# power_dist.net
KiCad netlist of a schematic drawn in EAGLE
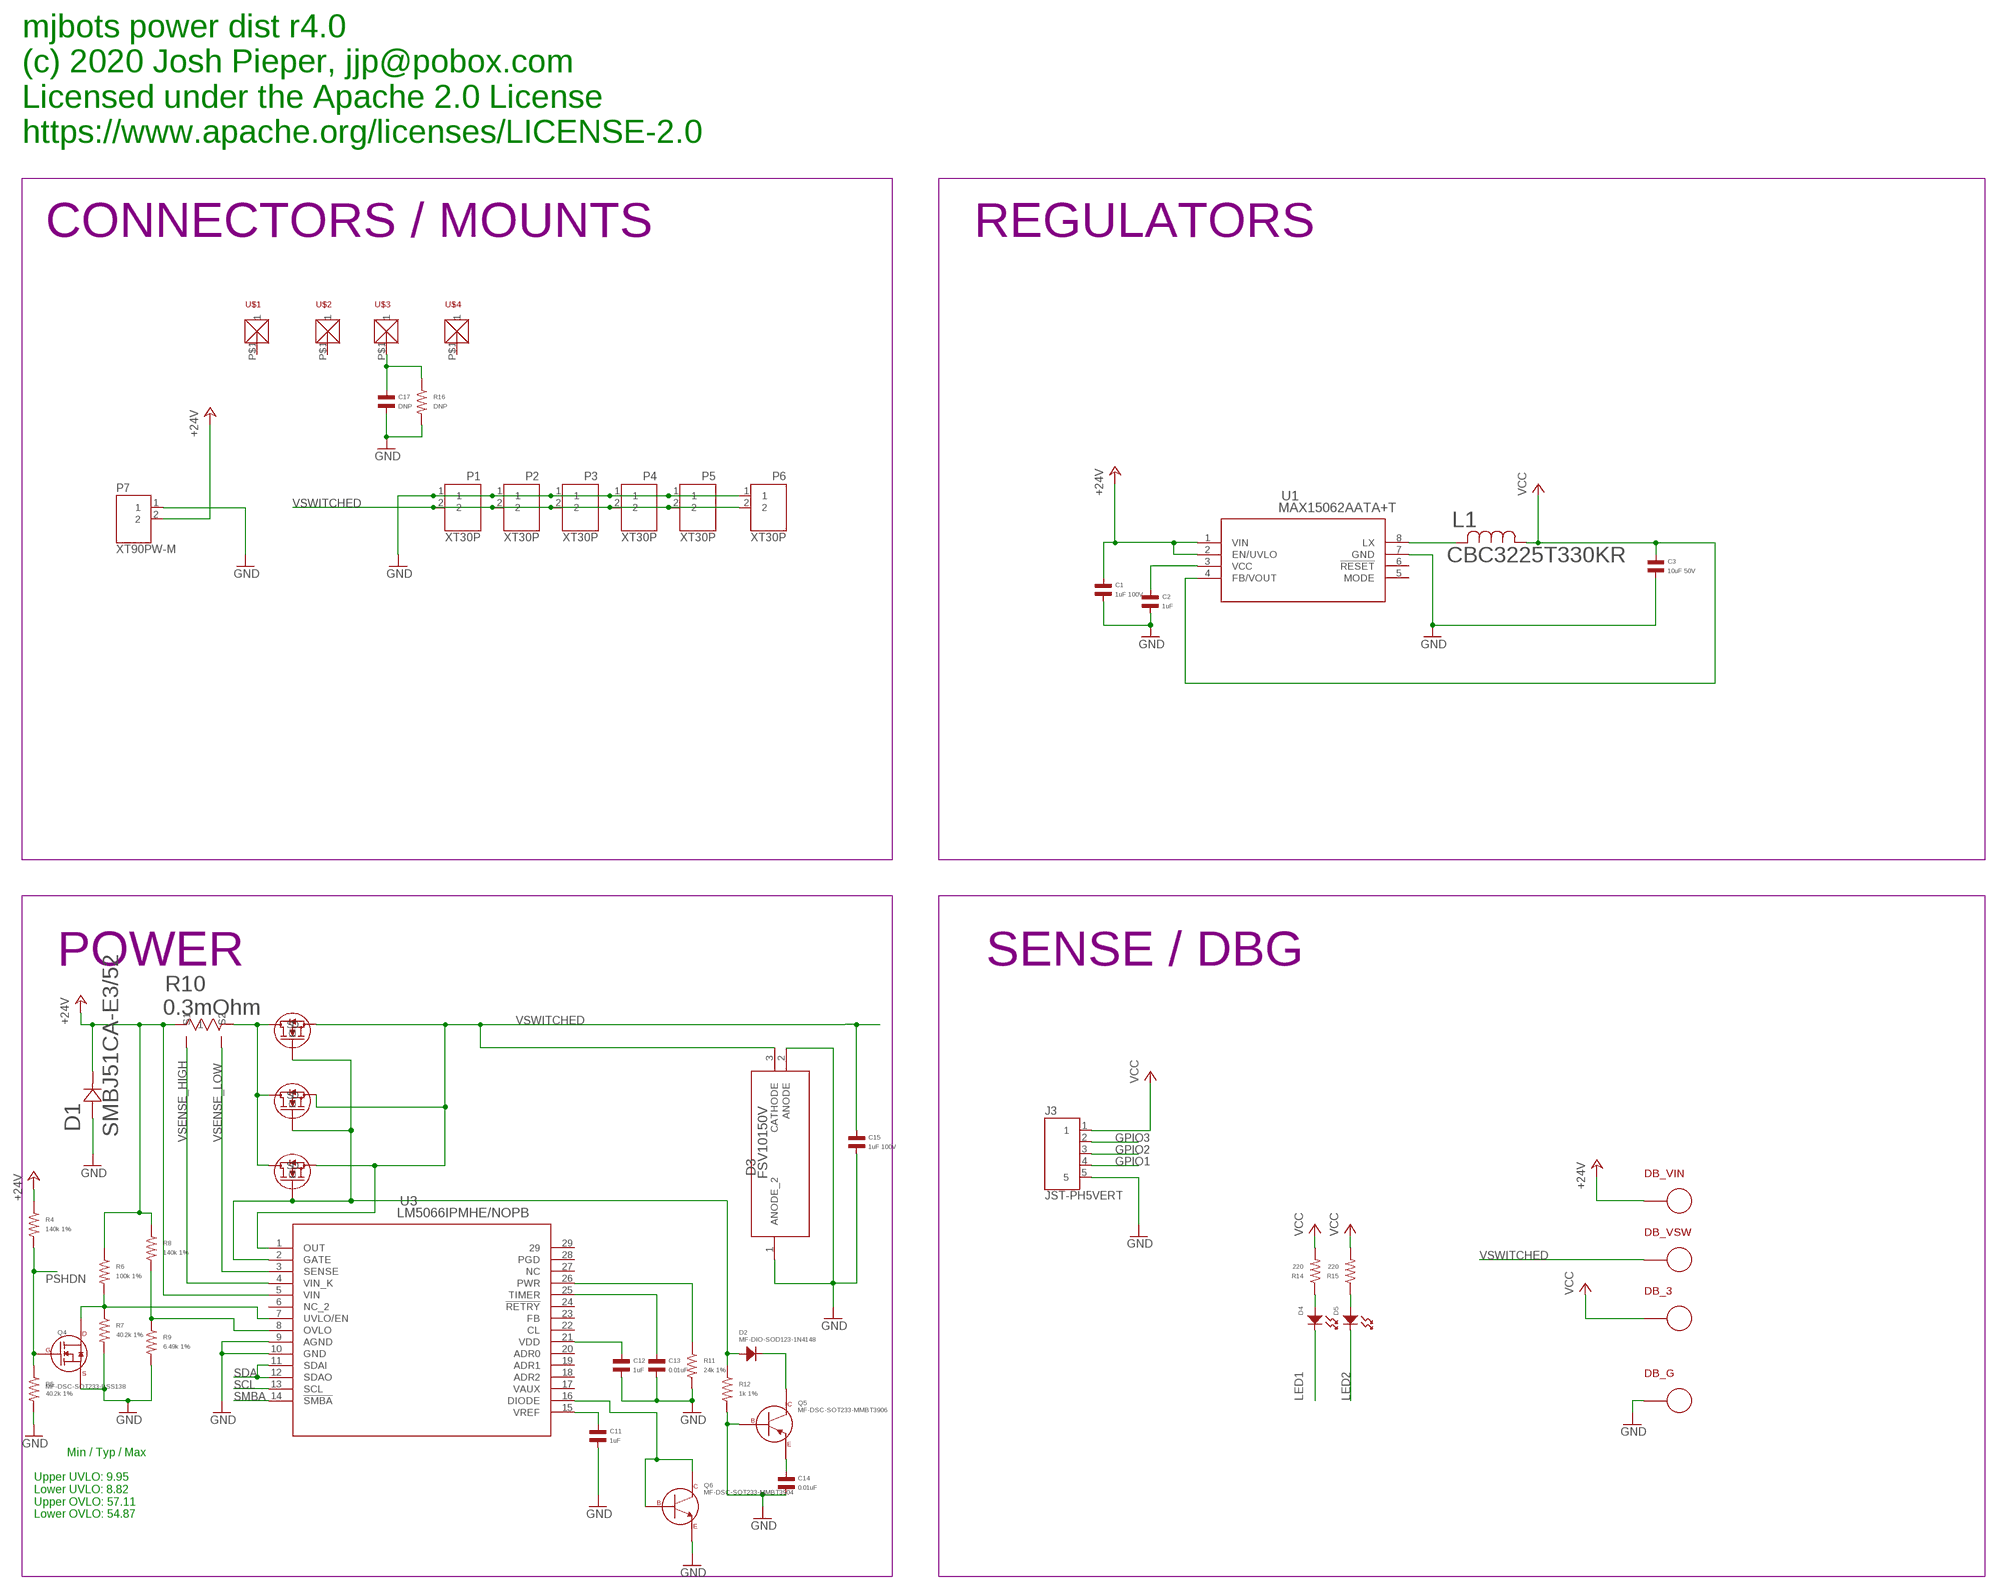
[diagram p0: schematic, sheet 1, part 1 of 2]
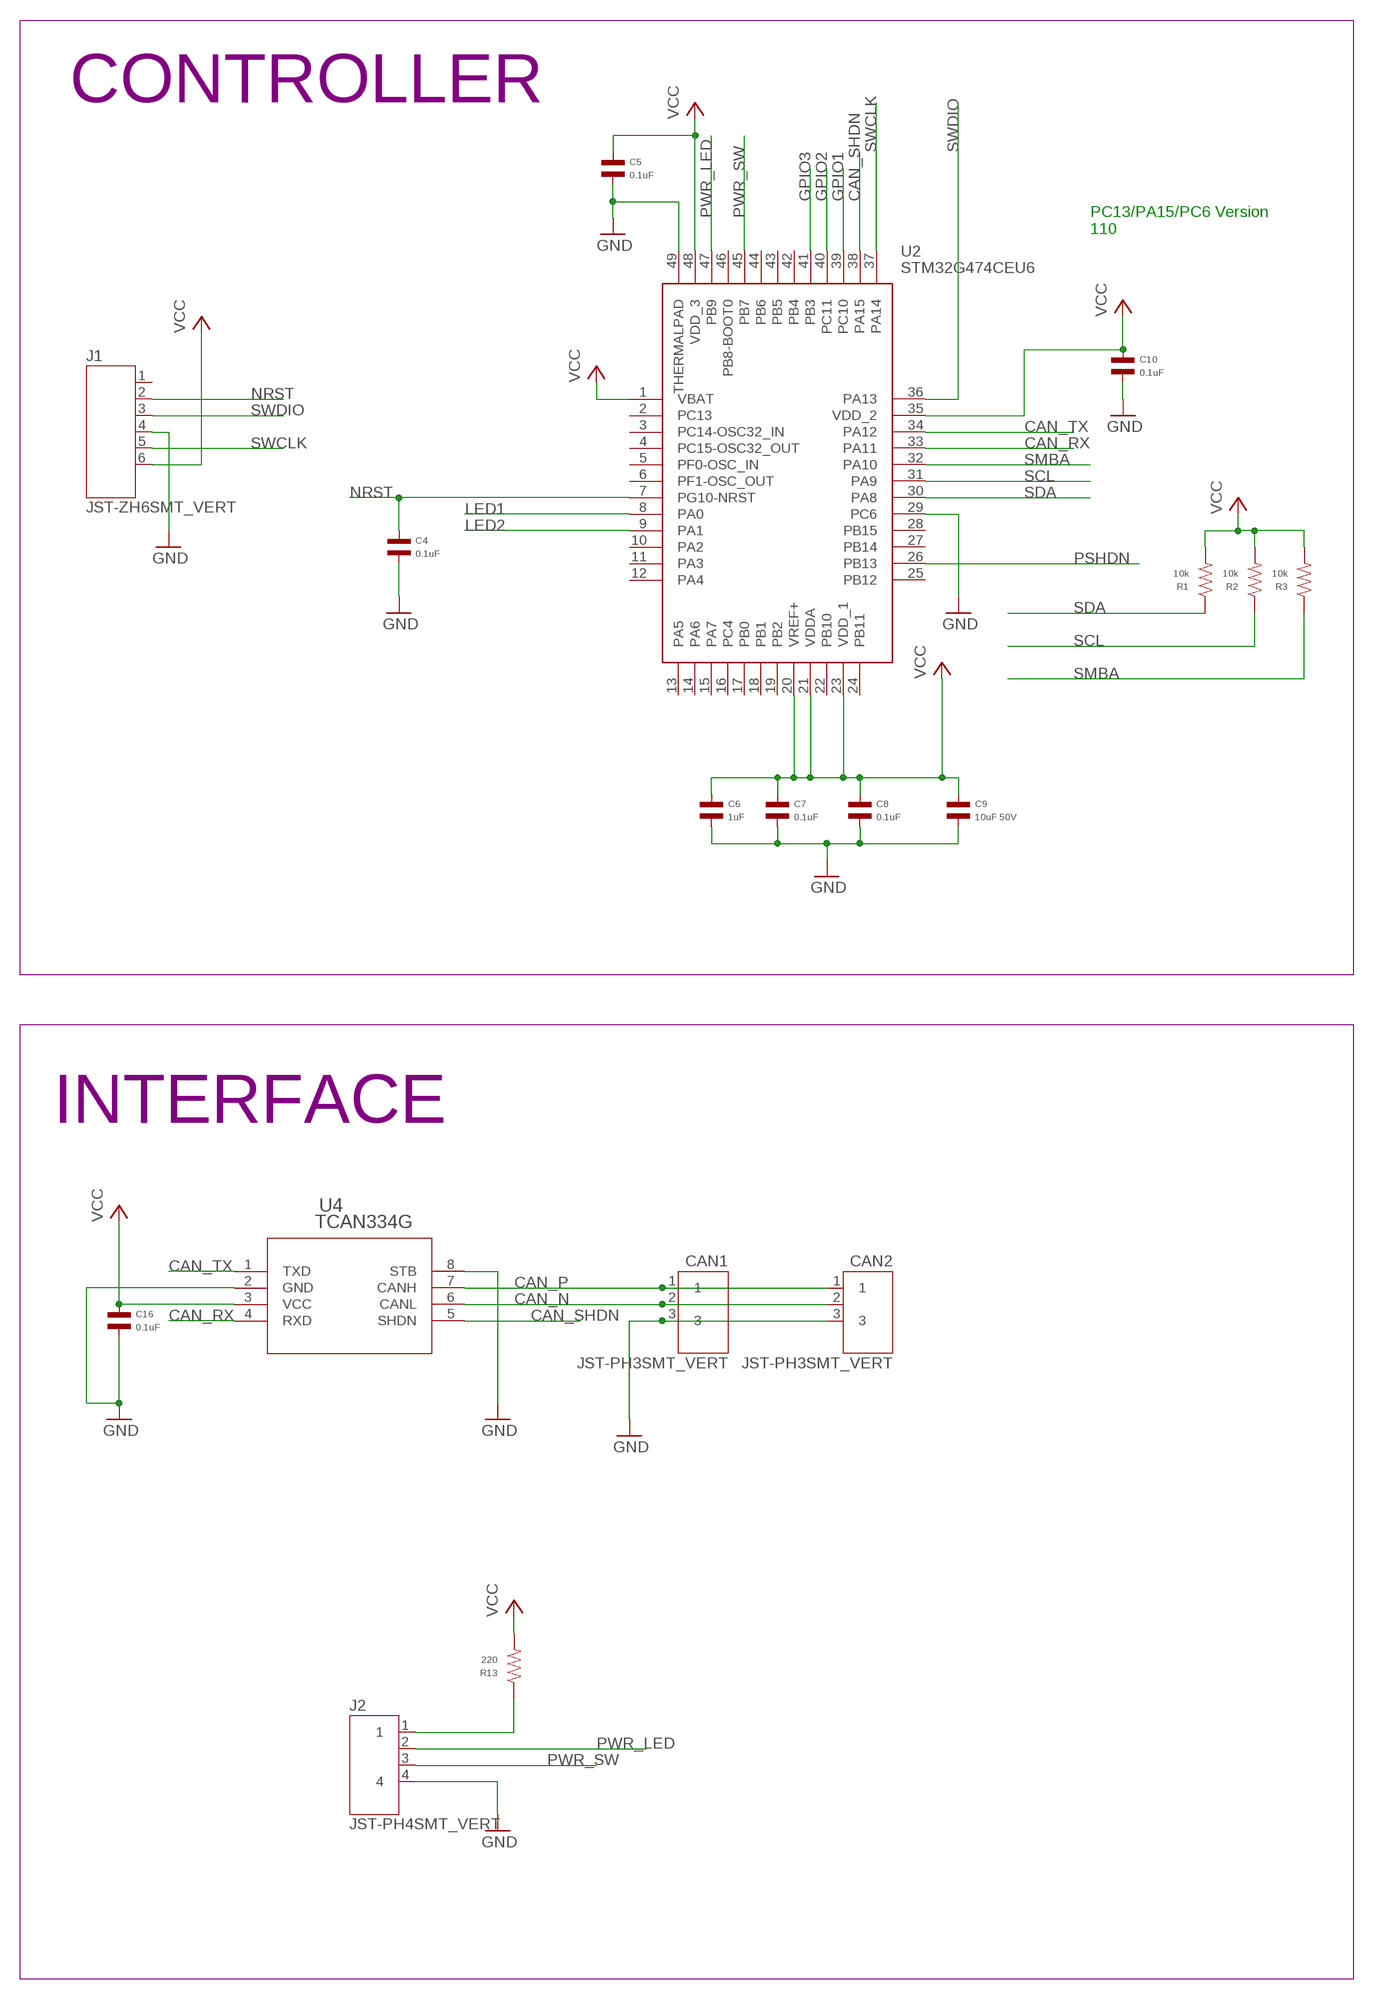
[diagram p1: schematic, sheet 1, part 2 of 2]

(export (version "E")
  (design (tool "Eeschema 10.0.6"))
  (components
    (comp (ref "C1")
      (value "1uF 100V")
      (footprint "eagle-import:C0805")
      (fields (field (name "MF") "MURATA") (field (name "MPN") "GCM21BC72A105KE36L"))
      (libsource (lib "eagle-import") (part "CAPACITOR_NP_0805"))
    )
    (comp (ref "C2")
      (value "1uF")
      (footprint "eagle-import:C0603")
      (fields (field (name "HOUSEPART") "1") (field (name "MPN") "MF-CAP-0603-1uF"))
      (libsource (lib "eagle-import") (part "CAPACITOR_NP_0603"))
    )
    (comp (ref "C3")
      (value "10uF 50V")
      (footprint "eagle-import:C1206")
      (fields (field (name "MF") "TDK") (field (name "MPN") "C3216X7R1H106K160AE"))
      (libsource (lib "eagle-import") (part "CAPACITOR_NP_1206"))
    )
    (comp (ref "C4")
      (value "0.1uF")
      (footprint "eagle-import:C0603")
      (fields (field (name "HOUSEPART") "1") (field (name "MPN") "MF-CAP-0603-0.1uF"))
      (libsource (lib "eagle-import") (part "CAPACITOR_NP_0603"))
    )
    (comp (ref "C5")
      (value "0.1uF")
      (footprint "eagle-import:C0603")
      (fields (field (name "HOUSEPART") "1") (field (name "MPN") "MF-CAP-0603-0.1uF"))
      (libsource (lib "eagle-import") (part "CAPACITOR_NP_0603"))
    )
    (comp (ref "C6")
      (value "1uF")
      (footprint "eagle-import:C0603")
      (fields (field (name "HOUSEPART") "1") (field (name "MPN") "MF-CAP-0603-1uF"))
      (libsource (lib "eagle-import") (part "CAPACITOR_NP_0603"))
    )
    (comp (ref "C7")
      (value "0.1uF")
      (footprint "eagle-import:C0603")
      (fields (field (name "HOUSEPART") "1") (field (name "MPN") "MF-CAP-0603-0.1uF"))
      (libsource (lib "eagle-import") (part "CAPACITOR_NP_0603"))
    )
    (comp (ref "C8")
      (value "0.1uF")
      (footprint "eagle-import:C0603")
      (fields (field (name "HOUSEPART") "1") (field (name "MPN") "MF-CAP-0603-0.1uF"))
      (libsource (lib "eagle-import") (part "CAPACITOR_NP_0603"))
    )
    (comp (ref "C9")
      (value "10uF 50V")
      (footprint "eagle-import:C1206")
      (fields (field (name "MF") "TDK") (field (name "MPN") "C3216X7R1H106K160AE"))
      (libsource (lib "eagle-import") (part "CAPACITOR_NP_1206"))
    )
    (comp (ref "C10")
      (value "0.1uF")
      (footprint "eagle-import:C0603")
      (fields (field (name "HOUSEPART") "1") (field (name "MPN") "MF-CAP-0603-0.1uF"))
      (libsource (lib "eagle-import") (part "CAPACITOR_NP_0603"))
    )
    (comp (ref "C11")
      (value "1uF")
      (footprint "eagle-import:C0603")
      (fields (field (name "HOUSEPART") "1") (field (name "MPN") "MF-CAP-0603-1uF"))
      (libsource (lib "eagle-import") (part "CAPACITOR_NP_0603"))
    )
    (comp (ref "C12")
      (value "1uF")
      (footprint "eagle-import:C0603")
      (fields (field (name "HOUSEPART") "1") (field (name "MPN") "MF-CAP-0603-1uF"))
      (libsource (lib "eagle-import") (part "CAPACITOR_NP_0603"))
    )
    (comp (ref "C13")
      (value "0.01uF")
      (footprint "eagle-import:C0603")
      (fields (field (name "HOUSEPART") "1") (field (name "MPN") "MF-CAP-0603-0.01uF"))
      (libsource (lib "eagle-import") (part "CAPACITOR_NP_0603"))
    )
    (comp (ref "C14")
      (value "0.01uF")
      (footprint "eagle-import:C0603")
      (fields (field (name "HOUSEPART") "1") (field (name "MPN") "MF-CAP-0603-0.01uF"))
      (libsource (lib "eagle-import") (part "CAPACITOR_NP_0603"))
    )
    (comp (ref "C15")
      (value "1uF 100V")
      (footprint "eagle-import:C0805")
      (fields (field (name "MF") "MURATA") (field (name "MPN") "GCM21BC72A105KE36L"))
      (libsource (lib "eagle-import") (part "CAPACITOR_NP_0805"))
    )
    (comp (ref "C16")
      (value "0.1uF")
      (footprint "eagle-import:C0603")
      (fields (field (name "HOUSEPART") "1") (field (name "MPN") "MF-CAP-0603-0.1uF"))
      (libsource (lib "eagle-import") (part "CAPACITOR_NP_0603"))
    )
    (comp (ref "C17")
      (value "DNP")
      (footprint "eagle-import:C0603")
      (fields (field (name "POPULATE") "0"))
      (libsource (lib "eagle-import") (part "CAPACITOR_NP_0603"))
    )
    (comp (ref "CAN1")
      (value "JST-PH3SMT_VERT")
      (footprint "eagle-import:JST_B3B_PH-SM4-TB(LF)(SN)")
      (fields (field (name "MF") "JST") (field (name "MPN") "B3B-PH-SM4-TB(LF)(SN)"))
      (libsource (lib "eagle-import") (part "JST-PH3SMT_VERT"))
    )
    (comp (ref "CAN2")
      (value "JST-PH3SMT_VERT")
      (footprint "eagle-import:JST_B3B_PH-SM4-TB(LF)(SN)")
      (fields (field (name "MF") "JST") (field (name "MPN") "B3B-PH-SM4-TB(LF)(SN)"))
      (libsource (lib "eagle-import") (part "JST-PH3SMT_VERT"))
    )
    (comp (ref "D1")
      (value "SMBJ51CA-E3/52")
      (footprint "eagle-import:DIODE_DO-214AC")
      (libsource (lib "eagle-import") (part "SMBJ51CA-E3/52"))
    )
    (comp (ref "D2")
      (value "MF-DIO-SOD123-1N4148")
      (footprint "eagle-import:SOD-123")
      (fields (field (name "HOUSEPART") "YES") (field (name "HOUSEPART_1") "1"))
      (libsource (lib "eagle-import") (part "DIODES_SOD-123_1N4148"))
    )
    (comp (ref "D3")
      (value "FSV10150V")
      (footprint "eagle-import:TO277-3L_ONS")
      (fields (field (name "COPYRIGHT") "Copyright (C) 2018 Accelerated Designs. All rights reserved"))
      (libsource (lib "eagle-import") (part "FSV10150V"))
    )
    (comp (ref "D4")
      (value "LED_SINGLE-0603")
      (footprint "eagle-import:LED0603")
      (fields
        (field (name "HOUSEPART") "NO")
        (field (name "HOUSEPART_1") "1")
        (field (name "MPN") "MF-LED-0603-RED")
      )
      (libsource (lib "eagle-import") (part "LED_SINGLE-0603"))
    )
    (comp (ref "D5")
      (value "LED_SINGLE-0603")
      (footprint "eagle-import:LED0603")
      (fields
        (field (name "HOUSEPART") "NO")
        (field (name "HOUSEPART_1") "1")
        (field (name "MPN") "MF-LED-0603-RED")
      )
      (libsource (lib "eagle-import") (part "LED_SINGLE-0603"))
    )
    (comp (ref "DB_3")
      (value "PAD24AWG_PAD")
      (footprint "eagle-import:24AWG_PAD")
      (libsource (lib "eagle-import") (part "PAD24AWG_PAD"))
    )
    (comp (ref "DB_G")
      (value "PAD24AWG_PAD")
      (footprint "eagle-import:24AWG_PAD")
      (libsource (lib "eagle-import") (part "PAD24AWG_PAD"))
    )
    (comp (ref "DB_VIN")
      (value "PAD24AWG_PAD")
      (footprint "eagle-import:24AWG_PAD")
      (libsource (lib "eagle-import") (part "PAD24AWG_PAD"))
    )
    (comp (ref "DB_VSW")
      (value "PAD24AWG_PAD")
      (footprint "eagle-import:24AWG_PAD")
      (libsource (lib "eagle-import") (part "PAD24AWG_PAD"))
    )
    (comp (ref "J1")
      (value "JST-ZH6SMT_VERT")
      (footprint "eagle-import:JST_B6B-ZR-SM4-TF(LF)(SN)")
      (fields (field (name "MF") "JST") (field (name "MPN") "B6B-ZR-SM4-TF(LF)(SN)"))
      (libsource (lib "eagle-import") (part "JST-ZH6SMT_VERT"))
    )
    (comp (ref "J2")
      (value "JST-PH4SMT_VERT")
      (footprint "eagle-import:JST_B4B_PH-SM4-TB(LF)(SN)")
      (fields (field (name "MF") "JST") (field (name "MPN") "B4B-PH-SM4-TB(LF)(SN)"))
      (libsource (lib "eagle-import") (part "JST-PH4SMT_VERT"))
    )
    (comp (ref "J3")
      (value "JST-PH5VERT")
      (footprint "eagle-import:JST_B5B_PH-SM4-TB(LF)(SN)")
      (fields (field (name "MF") "JST") (field (name "MPN") "B5B-PH-SM4-TB(LF)(SN)"))
      (libsource (lib "eagle-import") (part "JST-PH5VERT"))
    )
    (comp (ref "L1")
      (value "CBC3225T330KR")
      (footprint "eagle-import:IND_TAIYO_CBC3225_TAY")
      (libsource (lib "eagle-import") (part "CBC3225T330KR"))
    )
    (comp (ref "P1")
      (value "XT30P")
      (footprint "eagle-import:XT30P")
      (fields (field (name "MF") "AMASS") (field (name "MPN") "XT30UPB-F"))
      (libsource (lib "eagle-import") (part "XT30P"))
    )
    (comp (ref "P2")
      (value "XT30P")
      (footprint "eagle-import:XT30P")
      (fields (field (name "MF") "AMASS") (field (name "MPN") "XT30UPB-F"))
      (libsource (lib "eagle-import") (part "XT30P"))
    )
    (comp (ref "P3")
      (value "XT30P")
      (footprint "eagle-import:XT30P")
      (fields (field (name "MF") "AMASS") (field (name "MPN") "XT30UPB-F"))
      (libsource (lib "eagle-import") (part "XT30P"))
    )
    (comp (ref "P4")
      (value "XT30P")
      (footprint "eagle-import:XT30P")
      (fields (field (name "MF") "AMASS") (field (name "MPN") "XT30UPB-F"))
      (libsource (lib "eagle-import") (part "XT30P"))
    )
    (comp (ref "P5")
      (value "XT30P")
      (footprint "eagle-import:XT30P")
      (fields (field (name "MF") "AMASS") (field (name "MPN") "XT30UPB-F"))
      (libsource (lib "eagle-import") (part "XT30P"))
    )
    (comp (ref "P6")
      (value "XT30P")
      (footprint "eagle-import:XT30P")
      (fields (field (name "MF") "AMASS") (field (name "MPN") "XT30UPB-F"))
      (libsource (lib "eagle-import") (part "XT30P"))
    )
    (comp (ref "P7")
      (value "XT90PW-M")
      (footprint "eagle-import:XT90PW-M")
      (libsource (lib "eagle-import") (part "XT90PW-M"))
    )
    (comp (ref "Q1")
      (value "PSMN4R8-100BSEJ")
      (footprint "eagle-import:D2PAK_SOT404_NEX")
      (fields (field (name "COPYRIGHT") "Copyright (C) 2018 Accelerated Designs. All rights reserved"))
      (libsource (lib "eagle-import") (part "PSMN4R8-100BSEJ"))
    )
    (comp (ref "Q2")
      (value "PSMN4R8-100BSEJ")
      (footprint "eagle-import:D2PAK_SOT404_NEX")
      (fields (field (name "COPYRIGHT") "Copyright (C) 2018 Accelerated Designs. All rights reserved"))
      (libsource (lib "eagle-import") (part "PSMN4R8-100BSEJ"))
    )
    (comp (ref "Q3")
      (value "PSMN4R8-100BSEJ")
      (footprint "eagle-import:D2PAK_SOT404_NEX")
      (fields (field (name "COPYRIGHT") "Copyright (C) 2018 Accelerated Designs. All rights reserved"))
      (libsource (lib "eagle-import") (part "PSMN4R8-100BSEJ"))
    )
    (comp (ref "Q4")
      (value "MF-DSC-SOT233-BSS138")
      (footprint "eagle-import:SOT-23-3")
      (fields (field (name "HOUSEPART") "YES") (field (name "HOUSEPART_1") "1"))
      (libsource (lib "eagle-import") (part "N-CHANNEL_FET_SOT-23-3_BSS138"))
    )
    (comp (ref "Q5")
      (value "MF-DSC-SOT233-MMBT3906")
      (footprint "eagle-import:SOT-23-3")
      (fields (field (name "HOUSEPART") "YES") (field (name "HOUSEPART_1") "1"))
      (libsource (lib "eagle-import") (part "PNP_BJT_SOT-23-3_MMBT3906"))
    )
    (comp (ref "Q6")
      (value "MF-DSC-SOT233-MMBT3904")
      (footprint "eagle-import:SOT-23-3")
      (fields (field (name "HOUSEPART") "YES") (field (name "HOUSEPART_1") "1"))
      (libsource (lib "eagle-import") (part "NPN_BJT_SOT-23-3MMBT3904"))
    )
    (comp (ref "R1")
      (value "10k")
      (footprint "eagle-import:R0603")
      (fields (field (name "HOUSEPART") "1") (field (name "MPN") "MF-RES-0603-10K"))
      (libsource (lib "eagle-import") (part "RESISTOR_0603"))
    )
    (comp (ref "R2")
      (value "10k")
      (footprint "eagle-import:R0603")
      (fields (field (name "HOUSEPART") "1") (field (name "MPN") "MF-RES-0603-10K"))
      (libsource (lib "eagle-import") (part "RESISTOR_0603"))
    )
    (comp (ref "R3")
      (value "10k")
      (footprint "eagle-import:R0603")
      (fields (field (name "HOUSEPART") "1") (field (name "MPN") "MF-RES-0603-10K"))
      (libsource (lib "eagle-import") (part "RESISTOR_0603"))
    )
    (comp (ref "R4")
      (value "140k 1%")
      (footprint "eagle-import:R0603")
      (fields (field (name "MF") "YAGEO") (field (name "MPN") "RC0603FR-07140KL"))
      (libsource (lib "eagle-import") (part "RESISTOR_0603"))
    )
    (comp (ref "R5")
      (value "40.2k 1%")
      (footprint "eagle-import:R0603")
      (fields (field (name "MF") "YAGEO") (field (name "MPN") "RC0603FR-0740K2L"))
      (libsource (lib "eagle-import") (part "RESISTOR_0603"))
    )
    (comp (ref "R6")
      (value "100k 1%")
      (footprint "eagle-import:R0603")
      (fields (field (name "MF") "YAGEO") (field (name "MPN") "RC0603FR-07100KL"))
      (libsource (lib "eagle-import") (part "RESISTOR_0603"))
    )
    (comp (ref "R7")
      (value "40.2k 1%")
      (footprint "eagle-import:R0603")
      (fields (field (name "MF") "YAGEO") (field (name "MPN") "RC0603FR-0740K2L"))
      (libsource (lib "eagle-import") (part "RESISTOR_0603"))
    )
    (comp (ref "R8")
      (value "140k 1%")
      (footprint "eagle-import:R0603")
      (fields (field (name "MF") "YAGEO") (field (name "MPN") "RC0603FR-07140KL"))
      (libsource (lib "eagle-import") (part "RESISTOR_0603"))
    )
    (comp (ref "R9")
      (value "6.49k 1%")
      (footprint "eagle-import:R0603")
      (fields (field (name "MF") "YAGEO") (field (name "MPN") "RC0603FR-076K49L"))
      (libsource (lib "eagle-import") (part "RESISTOR_0603"))
    )
    (comp (ref "R10")
      (value "0.3mOhm")
      (footprint "eagle-import:SHUNT2512")
      (fields (field (name "MF") "VISHAY DALE") (field (name "MPN") "WSLF2512L3000FEA"))
      (libsource (lib "eagle-import") (part "SENSE_RESISTOR2512"))
    )
    (comp (ref "R11")
      (value "24k 1%")
      (footprint "eagle-import:R0603")
      (fields (field (name "MF") "YAGEO") (field (name "MPN") "RC0603FR-0724KL"))
      (libsource (lib "eagle-import") (part "RESISTOR_0603"))
    )
    (comp (ref "R12")
      (value "1k 1%")
      (footprint "eagle-import:R0603")
      (fields (field (name "MF") "YAGEO") (field (name "MPN") "RC0603FR-071KL"))
      (libsource (lib "eagle-import") (part "RESISTOR_0603"))
    )
    (comp (ref "R13")
      (value "220")
      (footprint "eagle-import:R0603")
      (fields (field (name "HOUSEPART") "1") (field (name "MPN") "MF-RES-0603-220"))
      (libsource (lib "eagle-import") (part "RESISTOR_0603"))
    )
    (comp (ref "R14")
      (value "220")
      (footprint "eagle-import:R0603")
      (fields (field (name "HOUSEPART") "1") (field (name "MPN") "MF-RES-0603-220"))
      (libsource (lib "eagle-import") (part "RESISTOR_0603"))
    )
    (comp (ref "R15")
      (value "220")
      (footprint "eagle-import:R0603")
      (fields (field (name "HOUSEPART") "1") (field (name "MPN") "MF-RES-0603-220"))
      (libsource (lib "eagle-import") (part "RESISTOR_0603"))
    )
    (comp (ref "R16")
      (value "DNP")
      (footprint "eagle-import:R0603")
      (fields (field (name "POPULATE") "0"))
      (libsource (lib "eagle-import") (part "RESISTOR_0603"))
    )
    (comp (ref "U$1")
      (value "MOUNT")
      (footprint "eagle-import:M2.5MOUNT")
      (libsource (lib "eagle-import") (part "MOUNT"))
    )
    (comp (ref "U$2")
      (value "MOUNT")
      (footprint "eagle-import:M2.5MOUNT")
      (libsource (lib "eagle-import") (part "MOUNT"))
    )
    (comp (ref "U$3")
      (value "MOUNT")
      (footprint "eagle-import:M2.5MOUNT")
      (libsource (lib "eagle-import") (part "MOUNT"))
    )
    (comp (ref "U$4")
      (value "MOUNT")
      (footprint "eagle-import:M2.5MOUNT")
      (libsource (lib "eagle-import") (part "MOUNT"))
    )
    (comp (ref "U1")
      (value "MAX15062AATA+T")
      (footprint "eagle-import:21-0487A_MXM")
      (fields (field (name "COPYRIGHT") "Copyright (C) 2018 Accelerated Designs. All rights reserved"))
      (libsource (lib "eagle-import") (part "MAX15062AATA+T"))
    )
    (comp (ref "U2")
      (value "STM32G474CEU6")
      (footprint "eagle-import:QFN50P700X700X60-49N")
      (fields (field (name "MOUSER_PART_NUMBER") "511-STM32G474CEU6") (field (name "MF") "ST"))
      (libsource (lib "eagle-import") (part "STM32G474CEU6"))
    )
    (comp (ref "U3")
      (value "LM5066IPMHE/NOPB")
      (footprint "eagle-import:MXA28A_TEX")
      (fields (field (name "MANUFACTURER") "Texas Instruments") (field (name "MF") "TI"))
      (libsource (lib "eagle-import") (part "LM5066IPMHE/NOPB"))
    )
    (comp (ref "U4")
      (value "TCAN334G")
      (footprint "eagle-import:SOIC8")
      (fields (field (name "MF") "Analog") (field (name "MPN") "LTC2875IS8"))
      (libsource (lib "eagle-import") (part "TCAN334G"))
    )
  )
  (nets
    (net (code "1") (name "+24V") (class "Default")
      (node (ref "C1") (pin "P$1") (pinfunction "P$1_P$1") (pintype "passive"))
      (node (ref "D1") (pin "1") (pinfunction "1_1") (pintype "passive"))
      (node (ref "DB_VIN") (pin "P$1") (pinfunction "P$1_P$1") (pintype "bidirectional"))
      (node (ref "P7") (pin "2") (pinfunction "2_2") (pintype "passive"))
      (node (ref "R10") (pin "1") (pinfunction "1_1") (pintype "passive"))
      (node (ref "R4") (pin "P$1") (pinfunction "P$1_P$1") (pintype "passive"))
      (node (ref "R6") (pin "P$1") (pinfunction "P$1_P$1") (pintype "passive"))
      (node (ref "R8") (pin "P$1") (pinfunction "P$1_P$1") (pintype "passive"))
      (node (ref "U1") (pin "1") (pinfunction "VIN_1") (pintype "input"))
      (node (ref "U1") (pin "2") (pinfunction "EN/UVLO_2") (pintype "input"))
      (node (ref "U3") (pin "5") (pinfunction "VIN_5") (pintype "input"))
    )
    (net (code "2") (name "/CAN_N") (class "Default")
      (node (ref "CAN1") (pin "2") (pinfunction "2_2") (pintype "passive"))
      (node (ref "CAN2") (pin "2") (pinfunction "2_2") (pintype "passive"))
      (node (ref "U4") (pin "6") (pinfunction "CANL_6") (pintype "bidirectional"))
    )
    (net (code "3") (name "/CAN_P") (class "Default")
      (node (ref "CAN1") (pin "1") (pinfunction "1_1") (pintype "passive"))
      (node (ref "CAN2") (pin "1") (pinfunction "1_1") (pintype "passive"))
      (node (ref "U4") (pin "7") (pinfunction "CANH_7") (pintype "bidirectional"))
    )
    (net (code "4") (name "/CAN_RX") (class "Default")
      (node (ref "U2") (pin "33") (pinfunction "PA11_33") (pintype "bidirectional"))
      (node (ref "U4") (pin "4") (pinfunction "RXD_4") (pintype "output"))
    )
    (net (code "5") (name "/CAN_SHDN") (class "Default")
      (node (ref "U2") (pin "38") (pinfunction "PA15_38") (pintype "bidirectional"))
      (node (ref "U4") (pin "5") (pinfunction "SHDN_5") (pintype "input"))
    )
    (net (code "6") (name "/CAN_TX") (class "Default")
      (node (ref "U2") (pin "34") (pinfunction "PA12_34") (pintype "bidirectional"))
      (node (ref "U4") (pin "1") (pinfunction "TXD_1") (pintype "input"))
    )
    (net (code "7") (name "/GPIO1") (class "Default")
      (node (ref "J3") (pin "4") (pinfunction "4_4") (pintype "passive"))
      (node (ref "U2") (pin "39") (pinfunction "PC10_39") (pintype "bidirectional"))
    )
    (net (code "8") (name "/GPIO2") (class "Default")
      (node (ref "J3") (pin "3") (pinfunction "3_3") (pintype "passive"))
      (node (ref "U2") (pin "40") (pinfunction "PC11_40") (pintype "bidirectional"))
    )
    (net (code "9") (name "/GPIO3") (class "Default")
      (node (ref "J3") (pin "2") (pinfunction "2_2") (pintype "passive"))
      (node (ref "U2") (pin "41") (pinfunction "PB3_41") (pintype "bidirectional"))
    )
    (net (code "10") (name "/LED1") (class "Default")
      (node (ref "D4") (pin "CATHODE") (pinfunction "CATHODE_CATHODE") (pintype "power_in"))
      (node (ref "U2") (pin "8") (pinfunction "PA0_8") (pintype "bidirectional"))
    )
    (net (code "11") (name "/LED2") (class "Default")
      (node (ref "D5") (pin "CATHODE") (pinfunction "CATHODE_CATHODE") (pintype "power_in"))
      (node (ref "U2") (pin "9") (pinfunction "PA1_9") (pintype "bidirectional"))
    )
    (net (code "12") (name "/NRST") (class "Default")
      (node (ref "C4") (pin "P$1") (pinfunction "P$1_P$1") (pintype "passive"))
      (node (ref "J1") (pin "2") (pinfunction "2_2") (pintype "passive"))
      (node (ref "U2") (pin "7") (pinfunction "PG10-NRST_7") (pintype "bidirectional"))
    )
    (net (code "13") (name "/PGD") (class "Default")
      (node (ref "U3") (pin "28") (pinfunction "PGD_28") (pintype "power_in"))
    )
    (net (code "14") (name "/PSHDN") (class "Default")
      (node (ref "Q4") (pin "P$1") (pinfunction "GATE_P$1") (pintype "bidirectional"))
      (node (ref "R4") (pin "P$2") (pinfunction "P$2_P$2") (pintype "passive"))
      (node (ref "R5") (pin "P$1") (pinfunction "P$1_P$1") (pintype "passive"))
      (node (ref "U2") (pin "26") (pinfunction "PB13_26") (pintype "bidirectional"))
    )
    (net (code "15") (name "/PWR_LED") (class "Default")
      (node (ref "J2") (pin "2") (pinfunction "2_2") (pintype "passive"))
      (node (ref "U2") (pin "47") (pinfunction "PB9_47") (pintype "bidirectional"))
    )
    (net (code "16") (name "/PWR_SW") (class "Default")
      (node (ref "J2") (pin "3") (pinfunction "3_3") (pintype "passive"))
      (node (ref "U2") (pin "45") (pinfunction "PB7_45") (pintype "bidirectional"))
    )
    (net (code "17") (name "/SCL") (class "Default")
      (node (ref "R2") (pin "P$1") (pinfunction "P$1_P$1") (pintype "passive"))
      (node (ref "U2") (pin "31") (pinfunction "PA9_31") (pintype "bidirectional"))
      (node (ref "U3") (pin "13") (pinfunction "SCL_13") (pintype "passive"))
    )
    (net (code "18") (name "/SDA") (class "Default")
      (node (ref "R1") (pin "P$1") (pinfunction "P$1_P$1") (pintype "passive"))
      (node (ref "U2") (pin "30") (pinfunction "PA8_30") (pintype "bidirectional"))
      (node (ref "U3") (pin "11") (pinfunction "SDAI_11") (pintype "input"))
      (node (ref "U3") (pin "12") (pinfunction "SDAO_12") (pintype "output"))
    )
    (net (code "19") (name "/SMBA") (class "Default")
      (node (ref "R3") (pin "P$1") (pinfunction "P$1_P$1") (pintype "passive"))
      (node (ref "U2") (pin "32") (pinfunction "PA10_32") (pintype "bidirectional"))
      (node (ref "U3") (pin "14") (pinfunction "~{SMBA}_14") (pintype "passive"))
    )
    (net (code "20") (name "/SWCLK") (class "Default")
      (node (ref "J1") (pin "5") (pinfunction "5_5") (pintype "passive"))
      (node (ref "U2") (pin "37") (pinfunction "PA14_37") (pintype "bidirectional"))
    )
    (net (code "21") (name "/SWDIO") (class "Default")
      (node (ref "J1") (pin "3") (pinfunction "3_3") (pintype "passive"))
      (node (ref "U2") (pin "36") (pinfunction "PA13_36") (pintype "bidirectional"))
    )
    (net (code "22") (name "/VSENSE_HIGH") (class "Default")
      (node (ref "R10") (pin "3") (pinfunction "S1_3") (pintype "passive"))
      (node (ref "U3") (pin "4") (pinfunction "VIN_K_4") (pintype "input"))
    )
    (net (code "23") (name "/VSENSE_LOW") (class "Default")
      (node (ref "R10") (pin "4") (pinfunction "S2_4") (pintype "passive"))
      (node (ref "U3") (pin "3") (pinfunction "SENSE_3") (pintype "input"))
    )
    (net (code "24") (name "/VSWITCHED") (class "Default")
      (node (ref "C15") (pin "P$1") (pinfunction "P$1_P$1") (pintype "passive"))
      (node (ref "D3") (pin "3") (pinfunction "CATHODE_3") (pintype "passive"))
      (node (ref "DB_VSW") (pin "P$1") (pinfunction "P$1_P$1") (pintype "bidirectional"))
      (node (ref "P1") (pin "2") (pinfunction "2_2") (pintype "passive"))
      (node (ref "P2") (pin "2") (pinfunction "2_2") (pintype "passive"))
      (node (ref "P3") (pin "2") (pinfunction "2_2") (pintype "passive"))
      (node (ref "P4") (pin "2") (pinfunction "2_2") (pintype "passive"))
      (node (ref "P5") (pin "2") (pinfunction "2_2") (pintype "passive"))
      (node (ref "P6") (pin "2") (pinfunction "2_2") (pintype "passive"))
      (node (ref "Q1") (pin "3") (pinfunction "S_3") (pintype "passive"))
      (node (ref "Q2") (pin "3") (pinfunction "S_3") (pintype "passive"))
      (node (ref "Q3") (pin "3") (pinfunction "S_3") (pintype "passive"))
      (node (ref "U3") (pin "1") (pinfunction "OUT_1") (pintype "output"))
    )
    (net (code "25") (name "GND") (class "Default")
      (node (ref "C1") (pin "P$2") (pinfunction "P$2_P$2") (pintype "passive"))
      (node (ref "C10") (pin "P$2") (pinfunction "P$2_P$2") (pintype "passive"))
      (node (ref "C11") (pin "P$2") (pinfunction "P$2_P$2") (pintype "passive"))
      (node (ref "C12") (pin "P$2") (pinfunction "P$2_P$2") (pintype "passive"))
      (node (ref "C13") (pin "P$2") (pinfunction "P$2_P$2") (pintype "passive"))
      (node (ref "C14") (pin "P$2") (pinfunction "P$2_P$2") (pintype "passive"))
      (node (ref "C15") (pin "P$2") (pinfunction "P$2_P$2") (pintype "passive"))
      (node (ref "C16") (pin "P$2") (pinfunction "P$2_P$2") (pintype "passive"))
      (node (ref "C17") (pin "P$2") (pinfunction "P$2_P$2") (pintype "passive"))
      (node (ref "C2") (pin "P$2") (pinfunction "P$2_P$2") (pintype "passive"))
      (node (ref "C3") (pin "P$2") (pinfunction "P$2_P$2") (pintype "passive"))
      (node (ref "C4") (pin "P$2") (pinfunction "P$2_P$2") (pintype "passive"))
      (node (ref "C5") (pin "P$2") (pinfunction "P$2_P$2") (pintype "passive"))
      (node (ref "C6") (pin "P$2") (pinfunction "P$2_P$2") (pintype "passive"))
      (node (ref "C7") (pin "P$2") (pinfunction "P$2_P$2") (pintype "passive"))
      (node (ref "C8") (pin "P$2") (pinfunction "P$2_P$2") (pintype "passive"))
      (node (ref "C9") (pin "P$2") (pinfunction "P$2_P$2") (pintype "passive"))
      (node (ref "CAN1") (pin "3") (pinfunction "3_3") (pintype "passive"))
      (node (ref "CAN2") (pin "3") (pinfunction "3_3") (pintype "passive"))
      (node (ref "D1") (pin "2") (pinfunction "2_2") (pintype "passive"))
      (node (ref "D3") (pin "1") (pinfunction "ANODE_2_1") (pintype "passive"))
      (node (ref "D3") (pin "2") (pinfunction "ANODE_2") (pintype "passive"))
      (node (ref "DB_G") (pin "P$1") (pinfunction "P$1_P$1") (pintype "bidirectional"))
      (node (ref "J1") (pin "4") (pinfunction "4_4") (pintype "passive"))
      (node (ref "J2") (pin "4") (pinfunction "4_4") (pintype "passive"))
      (node (ref "J3") (pin "5") (pinfunction "5_5") (pintype "passive"))
      (node (ref "P1") (pin "1") (pinfunction "1_1") (pintype "passive"))
      (node (ref "P2") (pin "1") (pinfunction "1_1") (pintype "passive"))
      (node (ref "P3") (pin "1") (pinfunction "1_1") (pintype "passive"))
      (node (ref "P4") (pin "1") (pinfunction "1_1") (pintype "passive"))
      (node (ref "P5") (pin "1") (pinfunction "1_1") (pintype "passive"))
      (node (ref "P6") (pin "1") (pinfunction "1_1") (pintype "passive"))
      (node (ref "P7") (pin "1") (pinfunction "1_1") (pintype "passive"))
      (node (ref "Q4") (pin "P$2") (pinfunction "SOURCE_P$2") (pintype "bidirectional"))
      (node (ref "Q5") (pin "P$1") (pinfunction "BASE_P$1") (pintype "bidirectional"))
      (node (ref "Q6") (pin "P$2") (pinfunction "EMITTER_P$2") (pintype "bidirectional"))
      (node (ref "R11") (pin "P$2") (pinfunction "P$2_P$2") (pintype "passive"))
      (node (ref "R12") (pin "P$2") (pinfunction "P$2_P$2") (pintype "passive"))
      (node (ref "R16") (pin "P$2") (pinfunction "P$2_P$2") (pintype "passive"))
      (node (ref "R5") (pin "P$2") (pinfunction "P$2_P$2") (pintype "passive"))
      (node (ref "R7") (pin "P$2") (pinfunction "P$2_P$2") (pintype "passive"))
      (node (ref "R9") (pin "P$2") (pinfunction "P$2_P$2") (pintype "passive"))
      (node (ref "U1") (pin "7") (pinfunction "GND_7") (pintype "power_in"))
      (node (ref "U2") (pin "29") (pinfunction "PC6_29") (pintype "bidirectional"))
      (node (ref "U2") (pin "49") (pinfunction "THERMALPAD_49") (pintype "bidirectional"))
      (node (ref "U3") (pin "10") (pinfunction "GND_10") (pintype "power_in"))
      (node (ref "U3") (pin "9") (pinfunction "AGND_9") (pintype "power_in"))
      (node (ref "U4") (pin "2") (pinfunction "GND_2") (pintype "power_in"))
      (node (ref "U4") (pin "8") (pinfunction "STB_8") (pintype "input"))
    )
    (net (code "26") (name "Net-(D4-PadANODE)") (class "Default")
      (node (ref "D4") (pin "ANODE") (pinfunction "ANODE_ANODE") (pintype "power_in"))
      (node (ref "R14") (pin "P$1") (pinfunction "P$1_P$1") (pintype "passive"))
    )
    (net (code "27") (name "Net-(D5-PadANODE)") (class "Default")
      (node (ref "D5") (pin "ANODE") (pinfunction "ANODE_ANODE") (pintype "power_in"))
      (node (ref "R15") (pin "P$1") (pinfunction "P$1_P$1") (pintype "passive"))
    )
    (net (code "28") (name "Net-(J2-Pad1)") (class "Default")
      (node (ref "J2") (pin "1") (pinfunction "1_1") (pintype "passive"))
      (node (ref "R13") (pin "P$1") (pinfunction "P$1_P$1") (pintype "passive"))
    )
    (net (code "29") (name "Net-(Q1-D)") (class "Default")
      (node (ref "Q1") (pin "2") (pinfunction "D_2") (pintype "passive"))
      (node (ref "Q2") (pin "2") (pinfunction "D_2") (pintype "passive"))
      (node (ref "Q3") (pin "2") (pinfunction "D_2") (pintype "passive"))
      (node (ref "R10") (pin "2") (pinfunction "2_2") (pintype "passive"))
    )
    (net (code "30") (name "Net-(Q1-G)") (class "Default")
      (node (ref "D2") (pin "ANODE") (pinfunction "ANODE_ANODE") (pintype "bidirectional"))
      (node (ref "Q1") (pin "1") (pinfunction "G_1") (pintype "passive"))
      (node (ref "Q2") (pin "1") (pinfunction "G_1") (pintype "passive"))
      (node (ref "Q3") (pin "1") (pinfunction "G_1") (pintype "passive"))
      (node (ref "R12") (pin "P$1") (pinfunction "P$1_P$1") (pintype "passive"))
      (node (ref "U3") (pin "2") (pinfunction "GATE_2") (pintype "output"))
    )
    (net (code "31") (name "Net-(Q4-DRAIN)") (class "Default")
      (node (ref "Q4") (pin "P$3") (pinfunction "DRAIN_P$3") (pintype "bidirectional"))
      (node (ref "R6") (pin "P$2") (pinfunction "P$2_P$2") (pintype "passive"))
      (node (ref "R7") (pin "P$1") (pinfunction "P$1_P$1") (pintype "passive"))
      (node (ref "U3") (pin "7") (pinfunction "UVLO/EN_7") (pintype "passive"))
    )
    (net (code "32") (name "Net-(Q5-COLLECTOR)") (class "Default")
      (node (ref "D2") (pin "CATHODE") (pinfunction "CATHODE_CATHODE") (pintype "bidirectional"))
      (node (ref "Q5") (pin "P$3") (pinfunction "COLLECTOR_P$3") (pintype "bidirectional"))
    )
    (net (code "33") (name "Net-(Q5-EMITTER)") (class "Default")
      (node (ref "C14") (pin "P$1") (pinfunction "P$1_P$1") (pintype "passive"))
      (node (ref "Q5") (pin "P$2") (pinfunction "EMITTER_P$2") (pintype "bidirectional"))
    )
    (net (code "34") (name "Net-(Q6-BASE)") (class "Default")
      (node (ref "Q6") (pin "P$1") (pinfunction "BASE_P$1") (pintype "bidirectional"))
      (node (ref "Q6") (pin "P$3") (pinfunction "COLLECTOR_P$3") (pintype "bidirectional"))
      (node (ref "U3") (pin "16") (pinfunction "DIODE_16") (pintype "passive"))
    )
    (net (code "35") (name "Net-(U$3-1)") (class "Default")
      (node (ref "C17") (pin "P$1") (pinfunction "P$1_P$1") (pintype "passive"))
      (node (ref "R16") (pin "P$1") (pinfunction "P$1_P$1") (pintype "passive"))
      (node (ref "U$3") (pin "P$1") (pinfunction "1_P$1") (pintype "passive"))
    )
    (net (code "36") (name "Net-(U1-LX)") (class "Default")
      (node (ref "L1") (pin "2") (pinfunction "2_2") (pintype "passive"))
      (node (ref "U1") (pin "8") (pinfunction "LX_8") (pintype "passive"))
    )
    (net (code "37") (name "Net-(U1-VCC)") (class "Default")
      (node (ref "C2") (pin "P$1") (pinfunction "P$1_P$1") (pintype "passive"))
      (node (ref "U1") (pin "3") (pinfunction "VCC_3") (pintype "power_in"))
    )
    (net (code "38") (name "Net-(U3-OVLO)") (class "Default")
      (node (ref "R8") (pin "P$2") (pinfunction "P$2_P$2") (pintype "passive"))
      (node (ref "R9") (pin "P$1") (pinfunction "P$1_P$1") (pintype "passive"))
      (node (ref "U3") (pin "8") (pinfunction "OVLO_8") (pintype "input"))
    )
    (net (code "39") (name "Net-(U3-PWR)") (class "Default")
      (node (ref "R11") (pin "P$1") (pinfunction "P$1_P$1") (pintype "passive"))
      (node (ref "U3") (pin "26") (pinfunction "PWR_26") (pintype "power_in"))
    )
    (net (code "40") (name "Net-(U3-TIMER)") (class "Default")
      (node (ref "C13") (pin "P$1") (pinfunction "P$1_P$1") (pintype "passive"))
      (node (ref "U3") (pin "25") (pinfunction "TIMER_25") (pintype "passive"))
    )
    (net (code "41") (name "Net-(U3-VDD)") (class "Default")
      (node (ref "C12") (pin "P$1") (pinfunction "P$1_P$1") (pintype "passive"))
      (node (ref "U3") (pin "21") (pinfunction "VDD_21") (pintype "power_in"))
    )
    (net (code "42") (name "Net-(U3-VREF)") (class "Default")
      (node (ref "C11") (pin "P$1") (pinfunction "P$1_P$1") (pintype "passive"))
      (node (ref "U3") (pin "15") (pinfunction "VREF_15") (pintype "passive"))
    )
    (net (code "43") (name "VCC") (class "Default")
      (node (ref "C10") (pin "P$1") (pinfunction "P$1_P$1") (pintype "passive"))
      (node (ref "C16") (pin "P$1") (pinfunction "P$1_P$1") (pintype "passive"))
      (node (ref "C3") (pin "P$1") (pinfunction "P$1_P$1") (pintype "passive"))
      (node (ref "C5") (pin "P$1") (pinfunction "P$1_P$1") (pintype "passive"))
      (node (ref "C6") (pin "P$1") (pinfunction "P$1_P$1") (pintype "passive"))
      (node (ref "C7") (pin "P$1") (pinfunction "P$1_P$1") (pintype "passive"))
      (node (ref "C8") (pin "P$1") (pinfunction "P$1_P$1") (pintype "passive"))
      (node (ref "C9") (pin "P$1") (pinfunction "P$1_P$1") (pintype "passive"))
      (node (ref "DB_3") (pin "P$1") (pinfunction "P$1_P$1") (pintype "bidirectional"))
      (node (ref "J1") (pin "6") (pinfunction "6_6") (pintype "passive"))
      (node (ref "J3") (pin "1") (pinfunction "1_1") (pintype "passive"))
      (node (ref "L1") (pin "1") (pinfunction "1_1") (pintype "passive"))
      (node (ref "R1") (pin "P$2") (pinfunction "P$2_P$2") (pintype "passive"))
      (node (ref "R13") (pin "P$2") (pinfunction "P$2_P$2") (pintype "passive"))
      (node (ref "R14") (pin "P$2") (pinfunction "P$2_P$2") (pintype "passive"))
      (node (ref "R15") (pin "P$2") (pinfunction "P$2_P$2") (pintype "passive"))
      (node (ref "R2") (pin "P$2") (pinfunction "P$2_P$2") (pintype "passive"))
      (node (ref "R3") (pin "P$2") (pinfunction "P$2_P$2") (pintype "passive"))
      (node (ref "U1") (pin "4") (pinfunction "FB/VOUT_4") (pintype "bidirectional"))
      (node (ref "U2") (pin "1") (pinfunction "VBAT_1") (pintype "bidirectional"))
      (node (ref "U2") (pin "20") (pinfunction "VREF+_20") (pintype "bidirectional"))
      (node (ref "U2") (pin "21") (pinfunction "VDDA_21") (pintype "bidirectional"))
      (node (ref "U2") (pin "23") (pinfunction "VDD_1_23") (pintype "bidirectional"))
      (node (ref "U2") (pin "35") (pinfunction "VDD_2_35") (pintype "bidirectional"))
      (node (ref "U2") (pin "48") (pinfunction "VDD_3_48") (pintype "bidirectional"))
      (node (ref "U4") (pin "3") (pinfunction "VCC_3") (pintype "power_in"))
    )
    (net (code "44") (name "unconnected-(J1-Pad1)") (class "Default")
      (node (ref "J1") (pin "1") (pinfunction "1_1") (pintype "passive"))
    )
    (net (code "45") (name "unconnected-(U$1-1-PadP$1)") (class "Default")
      (node (ref "U$1") (pin "P$1") (pinfunction "1_P$1") (pintype "passive"))
    )
    (net (code "46") (name "unconnected-(U$2-1-PadP$1)") (class "Default")
      (node (ref "U$2") (pin "P$1") (pinfunction "1_P$1") (pintype "passive"))
    )
    (net (code "47") (name "unconnected-(U$4-1-PadP$1)") (class "Default")
      (node (ref "U$4") (pin "P$1") (pinfunction "1_P$1") (pintype "passive"))
    )
    (net (code "48") (name "unconnected-(U1-MODE-Pad5)") (class "Default")
      (node (ref "U1") (pin "5") (pinfunction "MODE_5") (pintype "input"))
    )
    (net (code "49") (name "unconnected-(U1-~{RESET}-Pad6)") (class "Default")
      (node (ref "U1") (pin "6") (pinfunction "~{RESET}_6") (pintype "output"))
    )
    (net (code "50") (name "unconnected-(U2-PA2-Pad10)") (class "Default")
      (node (ref "U2") (pin "10") (pinfunction "PA2_10") (pintype "bidirectional"))
    )
    (net (code "51") (name "unconnected-(U2-PA3-Pad11)") (class "Default")
      (node (ref "U2") (pin "11") (pinfunction "PA3_11") (pintype "bidirectional"))
    )
    (net (code "52") (name "unconnected-(U2-PA4-Pad12)") (class "Default")
      (node (ref "U2") (pin "12") (pinfunction "PA4_12") (pintype "bidirectional"))
    )
    (net (code "53") (name "unconnected-(U2-PA5-Pad13)") (class "Default")
      (node (ref "U2") (pin "13") (pinfunction "PA5_13") (pintype "bidirectional"))
    )
    (net (code "54") (name "unconnected-(U2-PA6-Pad14)") (class "Default")
      (node (ref "U2") (pin "14") (pinfunction "PA6_14") (pintype "bidirectional"))
    )
    (net (code "55") (name "unconnected-(U2-PA7-Pad15)") (class "Default")
      (node (ref "U2") (pin "15") (pinfunction "PA7_15") (pintype "bidirectional"))
    )
    (net (code "56") (name "unconnected-(U2-PB0-Pad17)") (class "Default")
      (node (ref "U2") (pin "17") (pinfunction "PB0_17") (pintype "bidirectional"))
    )
    (net (code "57") (name "unconnected-(U2-PB1-Pad18)") (class "Default")
      (node (ref "U2") (pin "18") (pinfunction "PB1_18") (pintype "bidirectional"))
    )
    (net (code "58") (name "unconnected-(U2-PB2-Pad19)") (class "Default")
      (node (ref "U2") (pin "19") (pinfunction "PB2_19") (pintype "bidirectional"))
    )
    (net (code "59") (name "unconnected-(U2-PB4-Pad42)") (class "Default")
      (node (ref "U2") (pin "42") (pinfunction "PB4_42") (pintype "bidirectional"))
    )
    (net (code "60") (name "unconnected-(U2-PB5-Pad43)") (class "Default")
      (node (ref "U2") (pin "43") (pinfunction "PB5_43") (pintype "bidirectional"))
    )
    (net (code "61") (name "unconnected-(U2-PB6-Pad44)") (class "Default")
      (node (ref "U2") (pin "44") (pinfunction "PB6_44") (pintype "bidirectional"))
    )
    (net (code "62") (name "unconnected-(U2-PB8-BOOT0-Pad46)") (class "Default")
      (node (ref "U2") (pin "46") (pinfunction "PB8-BOOT0_46") (pintype "bidirectional"))
    )
    (net (code "63") (name "unconnected-(U2-PB10-Pad22)") (class "Default")
      (node (ref "U2") (pin "22") (pinfunction "PB10_22") (pintype "bidirectional"))
    )
    (net (code "64") (name "unconnected-(U2-PB11-Pad24)") (class "Default")
      (node (ref "U2") (pin "24") (pinfunction "PB11_24") (pintype "bidirectional"))
    )
    (net (code "65") (name "unconnected-(U2-PB12-Pad25)") (class "Default")
      (node (ref "U2") (pin "25") (pinfunction "PB12_25") (pintype "bidirectional"))
    )
    (net (code "66") (name "unconnected-(U2-PB14-Pad27)") (class "Default")
      (node (ref "U2") (pin "27") (pinfunction "PB14_27") (pintype "bidirectional"))
    )
    (net (code "67") (name "unconnected-(U2-PB15-Pad28)") (class "Default")
      (node (ref "U2") (pin "28") (pinfunction "PB15_28") (pintype "bidirectional"))
    )
    (net (code "68") (name "unconnected-(U2-PC4-Pad16)") (class "Default")
      (node (ref "U2") (pin "16") (pinfunction "PC4_16") (pintype "bidirectional"))
    )
    (net (code "69") (name "unconnected-(U2-PC13-Pad2)") (class "Default")
      (node (ref "U2") (pin "2") (pinfunction "PC13_2") (pintype "bidirectional"))
    )
    (net (code "70") (name "unconnected-(U2-PC14-OSC32_IN-Pad3)") (class "Default")
      (node (ref "U2") (pin "3") (pinfunction "PC14-OSC32_IN_3") (pintype "bidirectional"))
    )
    (net (code "71") (name "unconnected-(U2-PC15-OSC32_OUT-Pad4)") (class "Default")
      (node (ref "U2") (pin "4") (pinfunction "PC15-OSC32_OUT_4") (pintype "bidirectional"))
    )
    (net (code "72") (name "unconnected-(U2-PF0-OSC_IN-Pad5)") (class "Default")
      (node (ref "U2") (pin "5") (pinfunction "PF0-OSC_IN_5") (pintype "bidirectional"))
    )
    (net (code "73") (name "unconnected-(U2-PF1-OSC_OUT-Pad6)") (class "Default")
      (node (ref "U2") (pin "6") (pinfunction "PF1-OSC_OUT_6") (pintype "bidirectional"))
    )
    (net (code "74") (name "unconnected-(U3-ADR0-Pad20)") (class "Default")
      (node (ref "U3") (pin "20") (pinfunction "ADR0_20") (pintype "passive"))
    )
    (net (code "75") (name "unconnected-(U3-ADR1-Pad19)") (class "Default")
      (node (ref "U3") (pin "19") (pinfunction "ADR1_19") (pintype "passive"))
    )
    (net (code "76") (name "unconnected-(U3-ADR2-Pad18)") (class "Default")
      (node (ref "U3") (pin "18") (pinfunction "ADR2_18") (pintype "passive"))
    )
    (net (code "77") (name "unconnected-(U3-CL-Pad22)") (class "Default")
      (node (ref "U3") (pin "22") (pinfunction "CL_22") (pintype "passive"))
    )
    (net (code "78") (name "unconnected-(U3-FB-Pad23)") (class "Default")
      (node (ref "U3") (pin "23") (pinfunction "FB_23") (pintype "output"))
    )
    (net (code "79") (name "unconnected-(U3-NC-Pad27)") (class "Default")
      (node (ref "U3") (pin "27") (pinfunction "NC_27") (pintype "no_connect"))
    )
    (net (code "80") (name "unconnected-(U3-NC_2-Pad6)") (class "Default")
      (node (ref "U3") (pin "6") (pinfunction "NC_2_6") (pintype "no_connect"))
    )
    (net (code "81") (name "unconnected-(U3-Pad29)") (class "Default")
      (node (ref "U3") (pin "29") (pinfunction "29_29") (pintype "passive"))
    )
    (net (code "82") (name "unconnected-(U3-VAUX-Pad17)") (class "Default")
      (node (ref "U3") (pin "17") (pinfunction "VAUX_17") (pintype "input"))
    )
    (net (code "83") (name "unconnected-(U3-~{RETRY}-Pad24)") (class "Default")
      (node (ref "U3") (pin "24") (pinfunction "~{RETRY}_24") (pintype "input"))
    )
  )
)
